# ANT.net
KiCad netlist of a schematic drawn in Altium Designer
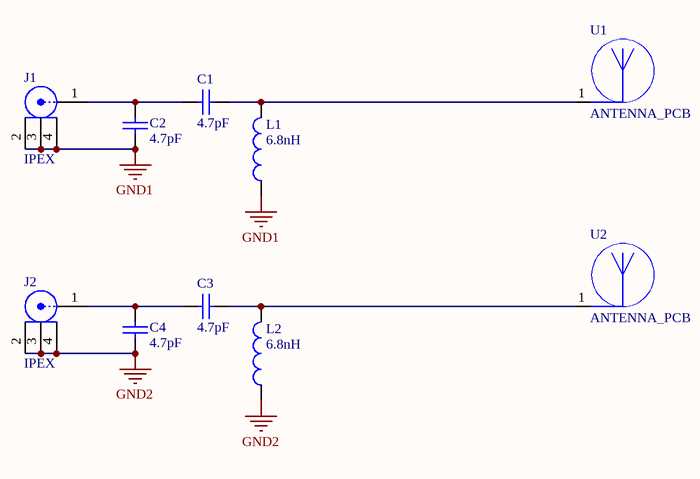
[diagram p0: ANT.SchDoc]

(export (version "E")
  (design (tool "Eeschema 10.0.6"))
  (components
    (comp (ref "C1")
      (value "4.7pF")
      (footprint "R0603_C")
      (description "精度 ±0.25pF \r\n容值 4.7pF \r\n额定电压 100V \r\n温漂系数（介质材料) C0G")
      (libsource (lib "00Lib") (part "4.7pF/0603/100V"))
    )
    (comp (ref "C2")
      (value "4.7pF")
      (footprint "R0603_C")
      (description "精度 ±0.25pF \r\n容值 4.7pF \r\n额定电压 100V \r\n温漂系数（介质材料) C0G")
      (libsource (lib "00Lib") (part "4.7pF/0603/100V"))
    )
    (comp (ref "C3")
      (value "4.7pF")
      (footprint "R0603_C")
      (description "精度 ±0.25pF \r\n容值 4.7pF \r\n额定电压 100V \r\n温漂系数（介质材料) C0G")
      (libsource (lib "00Lib") (part "4.7pF/0603/100V"))
    )
    (comp (ref "C4")
      (value "4.7pF")
      (footprint "R0603_C")
      (description "精度 ±0.25pF \r\n容值 4.7pF \r\n额定电压 100V \r\n温漂系数（介质材料) C0G")
      (libsource (lib "00Lib") (part "4.7pF/0603/100V"))
    )
    (comp (ref "J1")
      (value "IPEX")
      (footprint "molex-73412")
      (description "RF同轴连接器（天线座）")
      (libsource (lib "00Lib") (part "73412-0110"))
    )
    (comp (ref "J2")
      (value "IPEX")
      (footprint "molex-73412")
      (description "RF同轴连接器（天线座）")
      (libsource (lib "00Lib") (part "73412-0110"))
    )
    (comp (ref "L1")
      (value "6.8nH")
      (footprint "R0603_L")
      (description "高频电感 \r\n精度 ±0.2nH \r\n额定电流 200mA \r\n直流电阻（内阻） 700mΩ \r\n电感值 6.8nH")
      (libsource (lib "00Lib") (part "6.8nH/0603"))
    )
    (comp (ref "L2")
      (value "6.8nH")
      (footprint "R0603_L")
      (description "高频电感 \r\n精度 ±0.2nH \r\n额定电流 200mA \r\n直流电阻（内阻） 700mΩ \r\n电感值 6.8nH")
      (libsource (lib "00Lib") (part "6.8nH/0603"))
    )
    (comp (ref "U1")
      (value "ANTENNA_PCB")
      (footprint "ANTENNA_HELICAL")
      (libsource (lib "00Lib") (part "ANTENNA_DN024"))
    )
    (comp (ref "U2")
      (value "ANTENNA_PCB")
      (footprint "ANTENNA_HELICAL")
      (libsource (lib "00Lib") (part "ANTENNA_DN024"))
    )
  )
  (nets
    (net (code "1") (name "GND1") (class "Default")
      (node (ref "C2") (pin "1") (pinfunction "1_1") (pintype "passive"))
      (node (ref "J1") (pin "2") (pinfunction "2_2") (pintype "passive"))
      (node (ref "J1") (pin "3") (pinfunction "3_3") (pintype "passive"))
      (node (ref "J1") (pin "4") (pinfunction "4_4") (pintype "passive"))
      (node (ref "L1") (pin "1") (pinfunction "1_1") (pintype "passive"))
    )
    (net (code "2") (name "GND2") (class "Default")
      (node (ref "C4") (pin "2") (pinfunction "2_2") (pintype "passive"))
      (node (ref "J2") (pin "2") (pinfunction "2_2") (pintype "passive"))
      (node (ref "J2") (pin "3") (pinfunction "3_3") (pintype "passive"))
      (node (ref "J2") (pin "4") (pinfunction "4_4") (pintype "passive"))
      (node (ref "L2") (pin "1") (pinfunction "1_1") (pintype "passive"))
    )
    (net (code "3") (name "Net-(C1-Pad1)") (class "Default")
      (node (ref "C1") (pin "1") (pinfunction "1_1") (pintype "passive"))
      (node (ref "C2") (pin "2") (pinfunction "2_2") (pintype "passive"))
      (node (ref "J1") (pin "1") (pinfunction "1_1") (pintype "passive"))
    )
    (net (code "4") (name "Net-(C1-Pad2)") (class "Default")
      (node (ref "C1") (pin "2") (pinfunction "2_2") (pintype "passive"))
      (node (ref "L1") (pin "2") (pinfunction "2_2") (pintype "passive"))
      (node (ref "U1") (pin "1") (pinfunction "1_1") (pintype "passive"))
    )
    (net (code "5") (name "Net-(C3-Pad1)") (class "Default")
      (node (ref "C3") (pin "1") (pinfunction "1_1") (pintype "passive"))
      (node (ref "L2") (pin "2") (pinfunction "2_2") (pintype "passive"))
      (node (ref "U2") (pin "1") (pinfunction "1_1") (pintype "passive"))
    )
    (net (code "6") (name "Net-(C3-Pad2)") (class "Default")
      (node (ref "C3") (pin "2") (pinfunction "2_2") (pintype "passive"))
      (node (ref "C4") (pin "1") (pinfunction "1_1") (pintype "passive"))
      (node (ref "J2") (pin "1") (pinfunction "1_1") (pintype "passive"))
    )
  )
)
